# TheStaticTurtle_oshw-sdi3g-fiber__schema.net
KiCad netlist of a schematic drawn in Altium Designer
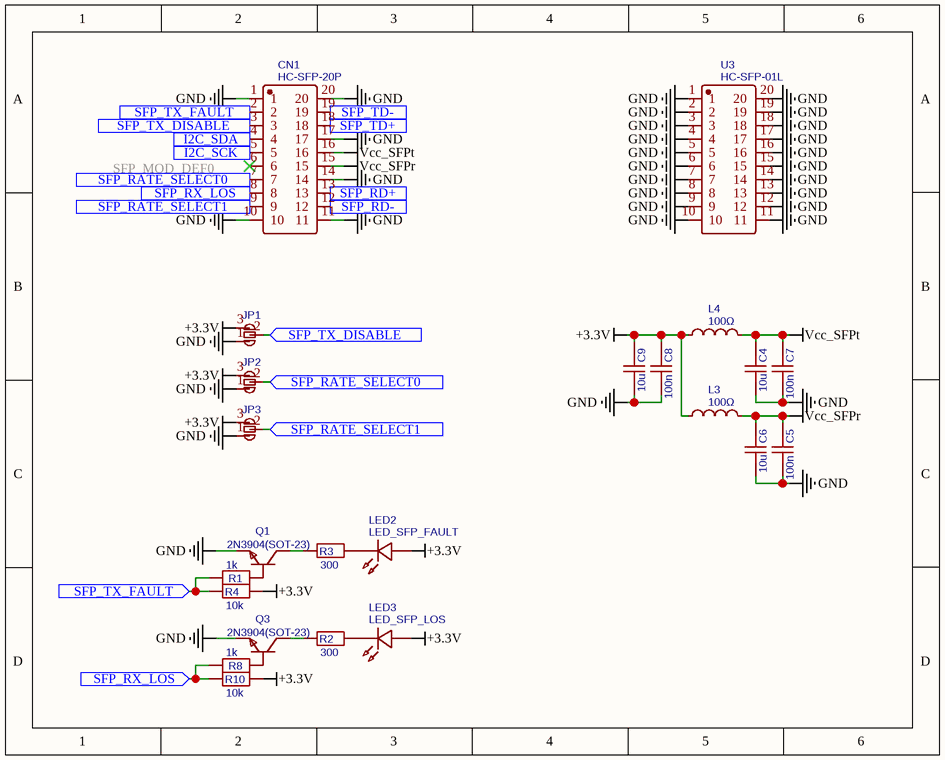
[diagram p0: TheStaticTurtle_oshw-sdi3g-fiber__schematic_V4-Normal_OSHW_BiDi_SDI_Fiber_Converter_V4_Normal_2024-11-17__SFP.schdoc]

(export (version "E")
  (design (tool "Eeschema 10.0.6"))
  (components
    (comp (ref "C4")
      (value "10u")
      (fields (field (name "CONTRIBUTOR") "LCEDA_Lib"))
      (libsource (lib "altium-import") (part "root_1_10u_"))
    )
    (comp (ref "C5")
      (value "100n")
      (fields (field (name "CONTRIBUTOR") "LCEDA_Lib"))
      (libsource (lib "altium-import") (part "root_1_100n_"))
    )
    (comp (ref "C6")
      (value "10u")
      (fields (field (name "CONTRIBUTOR") "LCEDA_Lib"))
      (libsource (lib "altium-import") (part "root_1_10u_"))
    )
    (comp (ref "C7")
      (value "100n")
      (fields (field (name "CONTRIBUTOR") "LCEDA_Lib"))
      (libsource (lib "altium-import") (part "root_1_100n_"))
    )
    (comp (ref "C8")
      (value "100n")
      (fields (field (name "CONTRIBUTOR") "LCEDA_Lib"))
      (libsource (lib "altium-import") (part "root_1_100n_"))
    )
    (comp (ref "C9")
      (value "10u")
      (fields (field (name "CONTRIBUTOR") "LCEDA_Lib"))
      (libsource (lib "altium-import") (part "root_1_10u_"))
    )
    (comp (ref "CN1")
      (value "HC-SFP-20P")
      (fields (field (name "MANUFACTURER") "HCTL(华灿天禄)") (field (name "CONTRIBUTOR") "LCSC"))
      (libsource (lib "altium-import") (part "root_0_HC-SFP-20P_"))
    )
    (comp (ref "JP1")
      (value "SOLDER BRIDGE 3P")
      (fields (field (name "CONTRIBUTOR") "TheStaticTurtle"))
      (libsource (lib "altium-import") (part "root_0_SOLDER BRIDGE 3P_"))
    )
    (comp (ref "JP2")
      (value "SOLDER BRIDGE 3P")
      (fields (field (name "CONTRIBUTOR") "TheStaticTurtle"))
      (libsource (lib "altium-import") (part "root_0_SOLDER BRIDGE 3P_"))
    )
    (comp (ref "JP3")
      (value "SOLDER BRIDGE 3P")
      (fields (field (name "CONTRIBUTOR") "TheStaticTurtle"))
      (libsource (lib "altium-import") (part "root_0_SOLDER BRIDGE 3P_"))
    )
    (comp (ref "L3")
      (value "100Ω")
      (fields (field (name "MANUFACTURER") "Sunlord(顺络)") (field (name "MANUFACTURER PART") "GZ2012D101TF"))
      (libsource (lib "altium-import") (part "root_0_100Ω_"))
    )
    (comp (ref "L4")
      (value "100Ω")
      (fields (field (name "MANUFACTURER") "Sunlord(顺络)") (field (name "MANUFACTURER PART") "GZ2012D101TF"))
      (libsource (lib "altium-import") (part "root_0_100Ω_"))
    )
    (comp (ref "LED2")
      (value "LED_SFP_FAULT")
      (fields
        (field (name "MANUFACTURER") "EVERLIGHT(台湾亿光)")
        (field (name "MANUFACTURER PART") "17-21SURC/S530-A3/TR8")
        (field (name "CONTRIBUTOR") "LCEDA_Lib")
      )
      (libsource (lib "altium-import") (part "root_2_LED_SFP_FAULT_"))
    )
    (comp (ref "LED3")
      (value "LED_SFP_LOS")
      (fields
        (field (name "MANUFACTURER") "EVERLIGHT(台湾亿光)")
        (field (name "MANUFACTURER PART") "17-21SURC/S530-A3/TR8")
        (field (name "CONTRIBUTOR") "LCEDA_Lib")
      )
      (libsource (lib "altium-import") (part "root_2_LED_SFP_LOS_"))
    )
    (comp (ref "Q1")
      (value "2N3904(SOT-23)")
      (fields
        (field (name "MANUFACTURER") "KEC")
        (field (name "MANUFACTURER PART") "2n3904S-RTK/PS")
        (field (name "CONTRIBUTOR") "LCEDA_Lib")
      )
      (libsource (lib "altium-import") (part "root_1_2N3904(SOT-23)_"))
    )
    (comp (ref "Q3")
      (value "2N3904(SOT-23)")
      (fields
        (field (name "MANUFACTURER") "KEC")
        (field (name "MANUFACTURER PART") "2n3904S-RTK/PS")
        (field (name "CONTRIBUTOR") "LCEDA_Lib")
      )
      (libsource (lib "altium-import") (part "root_1_2N3904(SOT-23)_"))
    )
    (comp (ref "R1")
      (value "1k")
      (fields (field (name "CONTRIBUTOR") "LCEDA_Lib"))
      (libsource (lib "altium-import") (part "root_2_1k_"))
    )
    (comp (ref "R2")
      (value "300")
      (fields (field (name "CONTRIBUTOR") "LCEDA_Lib"))
      (libsource (lib "altium-import") (part "root_2_300_"))
    )
    (comp (ref "R3")
      (value "300")
      (fields (field (name "CONTRIBUTOR") "LCEDA_Lib"))
      (libsource (lib "altium-import") (part "root_2_300_"))
    )
    (comp (ref "R4")
      (value "10k")
      (fields (field (name "CONTRIBUTOR") "LCEDA_Lib"))
      (libsource (lib "altium-import") (part "root_2_10k_"))
    )
    (comp (ref "R8")
      (value "1k")
      (fields (field (name "CONTRIBUTOR") "LCEDA_Lib"))
      (libsource (lib "altium-import") (part "root_2_1k_"))
    )
    (comp (ref "R10")
      (value "10k")
      (fields (field (name "CONTRIBUTOR") "LCEDA_Lib"))
      (libsource (lib "altium-import") (part "root_2_10k_"))
    )
    (comp (ref "U3")
      (value "HC-SFP-01L")
      (fields (field (name "MANUFACTURER") "HCTL(华灿天禄)") (field (name "CONTRIBUTOR") "LCSC"))
      (libsource (lib "altium-import") (part "root_0_HC-SFP-01L_"))
    )
  )
  (nets
    (net (code "1") (name "+3.3V") (class "Default")
      (node (ref "C8") (pin "2") (pinfunction "2_2") (pintype "passive"))
      (node (ref "C9") (pin "2") (pinfunction "2_2") (pintype "passive"))
      (node (ref "JP1") (pin "3") (pinfunction "B_3") (pintype "passive"))
      (node (ref "JP2") (pin "3") (pinfunction "B_3") (pintype "passive"))
      (node (ref "JP3") (pin "3") (pinfunction "B_3") (pintype "passive"))
      (node (ref "L3") (pin "1") (pinfunction "1_1") (pintype "passive"))
      (node (ref "L4") (pin "1") (pinfunction "1_1") (pintype "passive"))
      (node (ref "LED2") (pin "1") (pinfunction "1_1") (pintype "passive"))
      (node (ref "LED3") (pin "1") (pinfunction "1_1") (pintype "passive"))
      (node (ref "R10") (pin "1") (pinfunction "1_1") (pintype "passive"))
      (node (ref "R4") (pin "1") (pinfunction "1_1") (pintype "passive"))
    )
    (net (code "2") (name "/I2C_SCK") (class "Default")
      (node (ref "CN1") (pin "5") (pinfunction "5_5") (pintype "passive"))
    )
    (net (code "3") (name "/I2C_SDA") (class "Default")
      (node (ref "CN1") (pin "4") (pinfunction "4_4") (pintype "passive"))
    )
    (net (code "4") (name "/SFP_RATE_SELECT0") (class "Default")
      (node (ref "CN1") (pin "7") (pinfunction "7_7") (pintype "passive"))
      (node (ref "JP2") (pin "2") (pinfunction "B_2") (pintype "passive"))
    )
    (net (code "5") (name "/SFP_RATE_SELECT1") (class "Default")
      (node (ref "CN1") (pin "9") (pinfunction "9_9") (pintype "passive"))
      (node (ref "JP3") (pin "2") (pinfunction "B_2") (pintype "passive"))
    )
    (net (code "6") (name "/SFP_RD+") (class "Default")
      (node (ref "CN1") (pin "13") (pinfunction "13_13") (pintype "passive"))
    )
    (net (code "7") (name "/SFP_RD-") (class "Default")
      (node (ref "CN1") (pin "12") (pinfunction "12_12") (pintype "passive"))
    )
    (net (code "8") (name "/SFP_RX_LOS") (class "Default")
      (node (ref "CN1") (pin "8") (pinfunction "8_8") (pintype "passive"))
      (node (ref "R10") (pin "2") (pinfunction "2_2") (pintype "passive"))
      (node (ref "R8") (pin "2") (pinfunction "2_2") (pintype "passive"))
    )
    (net (code "9") (name "/SFP_TD+") (class "Default")
      (node (ref "CN1") (pin "18") (pinfunction "18_18") (pintype "passive"))
    )
    (net (code "10") (name "/SFP_TD-") (class "Default")
      (node (ref "CN1") (pin "19") (pinfunction "19_19") (pintype "passive"))
    )
    (net (code "11") (name "/SFP_TX_DISABLE") (class "Default")
      (node (ref "CN1") (pin "3") (pinfunction "3_3") (pintype "passive"))
      (node (ref "JP1") (pin "2") (pinfunction "B_2") (pintype "passive"))
    )
    (net (code "12") (name "/SFP_TX_FAULT") (class "Default")
      (node (ref "CN1") (pin "2") (pinfunction "2_2") (pintype "passive"))
      (node (ref "R1") (pin "2") (pinfunction "2_2") (pintype "passive"))
      (node (ref "R4") (pin "2") (pinfunction "2_2") (pintype "passive"))
    )
    (net (code "13") (name "GND") (class "Default")
      (node (ref "C4") (pin "1") (pinfunction "1_1") (pintype "passive"))
      (node (ref "C5") (pin "1") (pinfunction "1_1") (pintype "passive"))
      (node (ref "C6") (pin "1") (pinfunction "1_1") (pintype "passive"))
      (node (ref "C7") (pin "1") (pinfunction "1_1") (pintype "passive"))
      (node (ref "C8") (pin "1") (pinfunction "1_1") (pintype "passive"))
      (node (ref "C9") (pin "1") (pinfunction "1_1") (pintype "passive"))
      (node (ref "CN1") (pin "1") (pinfunction "1_1") (pintype "passive"))
      (node (ref "CN1") (pin "10") (pinfunction "10_10") (pintype "passive"))
      (node (ref "CN1") (pin "11") (pinfunction "11_11") (pintype "passive"))
      (node (ref "CN1") (pin "14") (pinfunction "14_14") (pintype "passive"))
      (node (ref "CN1") (pin "17") (pinfunction "17_17") (pintype "passive"))
      (node (ref "CN1") (pin "20") (pinfunction "20_20") (pintype "passive"))
      (node (ref "JP1") (pin "1") (pinfunction "A_1") (pintype "passive"))
      (node (ref "JP2") (pin "1") (pinfunction "A_1") (pintype "passive"))
      (node (ref "JP3") (pin "1") (pinfunction "A_1") (pintype "passive"))
      (node (ref "Q1") (pin "1") (pinfunction "E_1") (pintype "passive"))
      (node (ref "Q3") (pin "1") (pinfunction "E_1") (pintype "passive"))
      (node (ref "U3") (pin "1") (pinfunction "1_1") (pintype "passive"))
      (node (ref "U3") (pin "10") (pinfunction "10_10") (pintype "passive"))
      (node (ref "U3") (pin "11") (pinfunction "11_11") (pintype "passive"))
      (node (ref "U3") (pin "12") (pinfunction "12_12") (pintype "passive"))
      (node (ref "U3") (pin "13") (pinfunction "13_13") (pintype "passive"))
      (node (ref "U3") (pin "14") (pinfunction "14_14") (pintype "passive"))
      (node (ref "U3") (pin "15") (pinfunction "15_15") (pintype "passive"))
      (node (ref "U3") (pin "16") (pinfunction "16_16") (pintype "passive"))
      (node (ref "U3") (pin "17") (pinfunction "17_17") (pintype "passive"))
      (node (ref "U3") (pin "18") (pinfunction "18_18") (pintype "passive"))
      (node (ref "U3") (pin "19") (pinfunction "19_19") (pintype "passive"))
      (node (ref "U3") (pin "2") (pinfunction "2_2") (pintype "passive"))
      (node (ref "U3") (pin "20") (pinfunction "20_20") (pintype "passive"))
      (node (ref "U3") (pin "3") (pinfunction "3_3") (pintype "passive"))
      (node (ref "U3") (pin "4") (pinfunction "4_4") (pintype "passive"))
      (node (ref "U3") (pin "5") (pinfunction "5_5") (pintype "passive"))
      (node (ref "U3") (pin "6") (pinfunction "6_6") (pintype "passive"))
      (node (ref "U3") (pin "7") (pinfunction "7_7") (pintype "passive"))
      (node (ref "U3") (pin "8") (pinfunction "8_8") (pintype "passive"))
      (node (ref "U3") (pin "9") (pinfunction "9_9") (pintype "passive"))
    )
    (net (code "14") (name "Net-(LED2-Pad2)") (class "Default")
      (node (ref "LED2") (pin "2") (pinfunction "2_2") (pintype "passive"))
      (node (ref "R3") (pin "1") (pinfunction "1_1") (pintype "passive"))
    )
    (net (code "15") (name "Net-(LED3-Pad2)") (class "Default")
      (node (ref "LED3") (pin "2") (pinfunction "2_2") (pintype "passive"))
      (node (ref "R2") (pin "1") (pinfunction "1_1") (pintype "passive"))
    )
    (net (code "16") (name "Net-(Q1-B)") (class "Default")
      (node (ref "Q1") (pin "2") (pinfunction "B_2") (pintype "passive"))
      (node (ref "R1") (pin "1") (pinfunction "1_1") (pintype "passive"))
    )
    (net (code "17") (name "Net-(Q1-C)") (class "Default")
      (node (ref "Q1") (pin "3") (pinfunction "C_3") (pintype "passive"))
      (node (ref "R3") (pin "2") (pinfunction "2_2") (pintype "passive"))
    )
    (net (code "18") (name "Net-(Q3-B)") (class "Default")
      (node (ref "Q3") (pin "2") (pinfunction "B_2") (pintype "passive"))
      (node (ref "R8") (pin "1") (pinfunction "1_1") (pintype "passive"))
    )
    (net (code "19") (name "Net-(Q3-C)") (class "Default")
      (node (ref "Q3") (pin "3") (pinfunction "C_3") (pintype "passive"))
      (node (ref "R2") (pin "2") (pinfunction "2_2") (pintype "passive"))
    )
    (net (code "20") (name "Vcc_SFPr") (class "Default")
      (node (ref "C5") (pin "2") (pinfunction "2_2") (pintype "passive"))
      (node (ref "C6") (pin "2") (pinfunction "2_2") (pintype "passive"))
      (node (ref "CN1") (pin "15") (pinfunction "15_15") (pintype "passive"))
      (node (ref "L3") (pin "2") (pinfunction "2_2") (pintype "passive"))
    )
    (net (code "21") (name "Vcc_SFPt") (class "Default")
      (node (ref "C4") (pin "2") (pinfunction "2_2") (pintype "passive"))
      (node (ref "C7") (pin "2") (pinfunction "2_2") (pintype "passive"))
      (node (ref "CN1") (pin "16") (pinfunction "16_16") (pintype "passive"))
      (node (ref "L4") (pin "2") (pinfunction "2_2") (pintype "passive"))
    )
    (net (code "22") (name "unconnected-(CN1-Pad6)") (class "Default")
      (node (ref "CN1") (pin "6") (pinfunction "6_6") (pintype "passive+no_connect"))
    )
  )
)
